# 03_-_DAC8760.net
KiCad netlist of a schematic drawn in Altium Designer
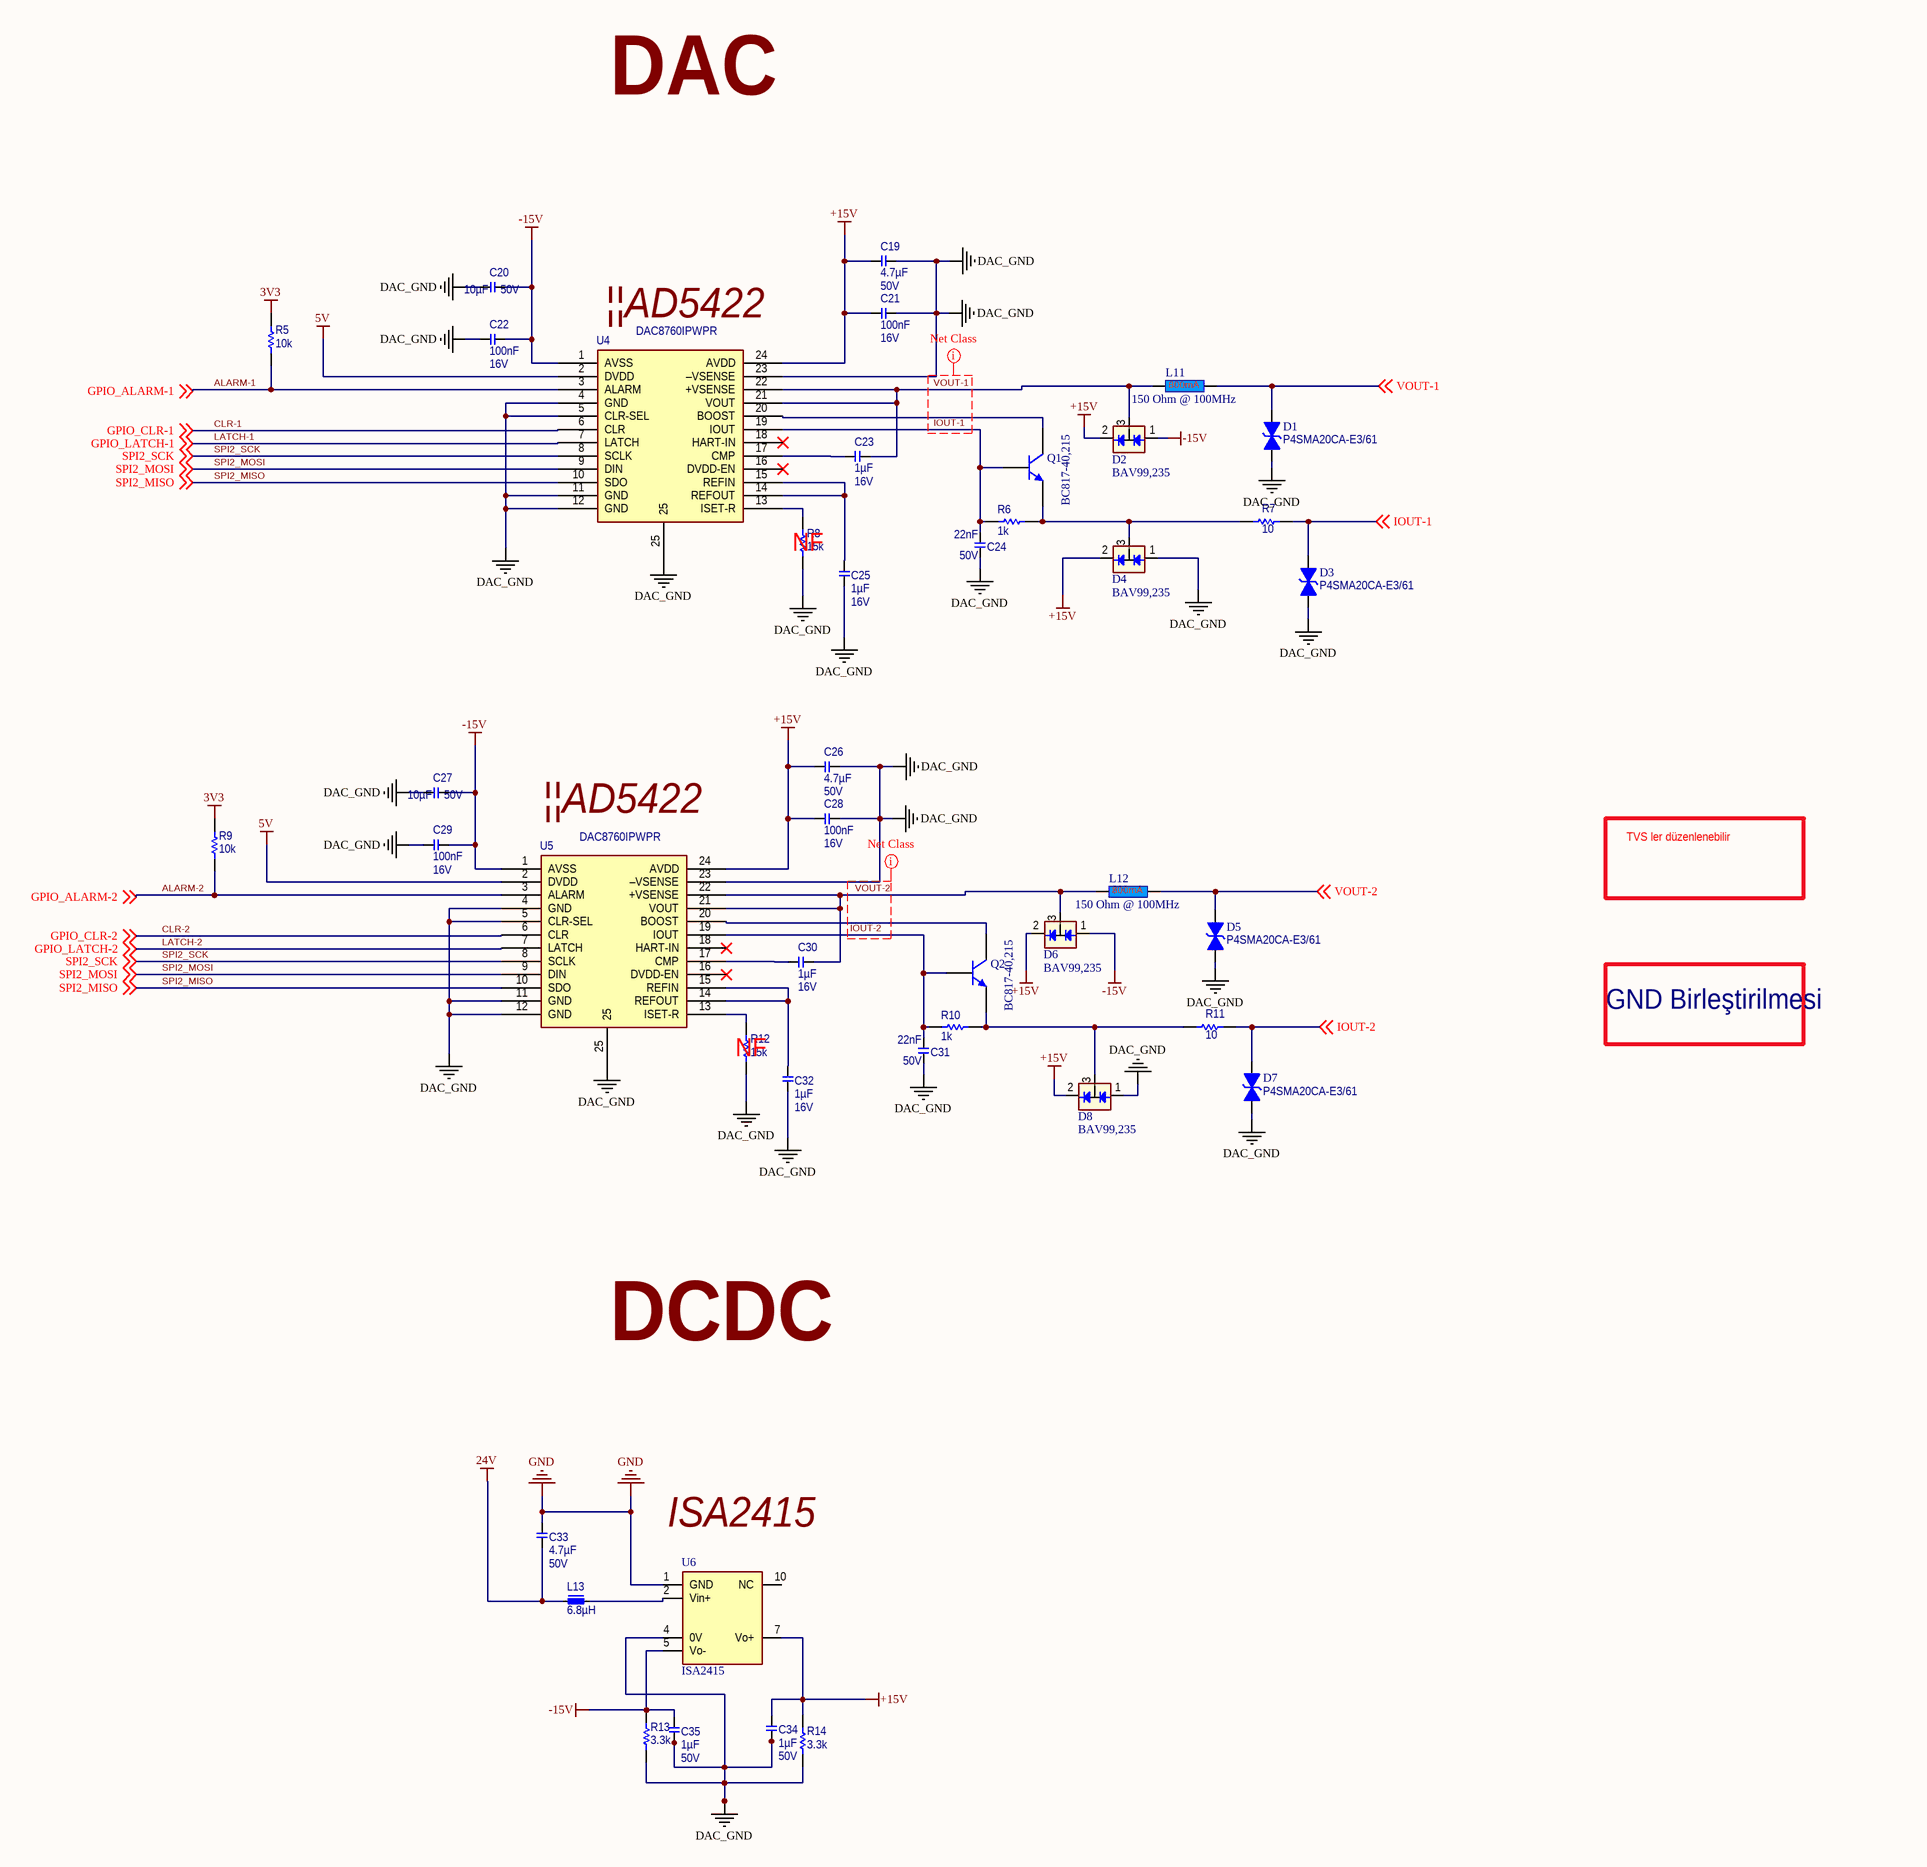
[diagram p0: [03] - DAC8760.SchDoc]

(export (version "E")
  (design (tool "Eeschema 10.0.6"))
  (components
    (comp (ref "C19")
      (value "4.7UF 50V X7R")
      (footprint "C1206")
      (description "CAP CER 4.7UF 50V X7R 1206")
      (fields
        (field (name "MANUFACTURER") "Samsung Electro-Mechanics America, Inc.")
        (field (name "MANUFACTURER PART NUMBER") "CL31B475KBHNNNE")
        (field (name "CAPACITANCE") "4.7µF")
        (field (name "VOLTAGE - RATED") "50V")
      )
      (libsource (lib "CPU_STM_080816") (part "C-4.7UF,50V,1206"))
    )
    (comp (ref "C20")
      (value "10UF 50V X5R")
      (footprint "C0805")
      (description "CAP CER 10UF 50V X7R 1206")
      (fields
        (field (name "MANUFACTURER") "Samsung Electro-Mechanics America, Inc.")
        (field (name "MANUFACTURER PART NUMBER") "CL31B106KBHNNNE")
        (field (name "CAPACITANCE") "10µF")
        (field (name "VOLTAGE - RATED") "50V")
      )
      (libsource (lib "CPU_STM_080816") (part "C-10UF,50V,0805"))
    )
    (comp (ref "C21")
      (value "100nF")
      (footprint "C0805")
      (description "AVX - 0805YA103JAT2A - CAP, MLCC, C0G/NP0, 10NF, 16V, 0805")
      (fields
        (field (name "MANUFACTURER") "AVX")
        (field (name "MANUFACTURER PART NUMBER") "0805YA103JAT2A")
        (field (name "CAPACITANCE") "100nF")
        (field (name "VOLTAGE - RATED") "16V")
      )
      (libsource (lib "CPU_STM_080816") (part "C-100NF,16V,0805"))
    )
    (comp (ref "C22")
      (value "100nF")
      (footprint "C0805")
      (description "AVX - 0805YA103JAT2A - CAP, MLCC, C0G/NP0, 10NF, 16V, 0805")
      (fields
        (field (name "MANUFACTURER") "AVX")
        (field (name "MANUFACTURER PART NUMBER") "0805YA103JAT2A")
        (field (name "CAPACITANCE") "100nF")
        (field (name "VOLTAGE - RATED") "16V")
      )
      (libsource (lib "CPU_STM_080816") (part "C-100NF,16V,0805"))
    )
    (comp (ref "C23")
      (value "1µF")
      (footprint "C0805")
      (description "AVX - 0805YC105KAT2A - CAP, MLCC, X7R, 1UF, 16V, 0805")
      (fields
        (field (name "MANUFACTURER") "AVX Corporation")
        (field (name "MANUFACTURER PART NUMBER") "0805YC105KAT2A")
        (field (name "CAPACITANCE") "1µF")
        (field (name "VOLTAGE - RATED") "16V")
      )
      (libsource (lib "CPU_STM_080816") (part "C-1UF,16V,0805"))
    )
    (comp (ref "C24")
      (value "22NF 50V X7R")
      (footprint "C0805")
      (description "CAP CER 0.022UF 50V X7R 0805")
      (fields
        (field (name "MANUFACTURER") "Kemet")
        (field (name "MANUFACTURER PART NUMBER") "C0805C223K5RACTU")
        (field (name "CAPACITANCE") "22nF")
        (field (name "VOLTAGE - RATED") "50V")
      )
      (libsource (lib "CPU_STM_080816") (part "C-22NF,50V"))
    )
    (comp (ref "C25")
      (value "1µF")
      (footprint "C0805")
      (description "AVX - 0805YC105KAT2A - CAP, MLCC, X7R, 1UF, 16V, 0805")
      (fields
        (field (name "MANUFACTURER") "AVX Corporation")
        (field (name "MANUFACTURER PART NUMBER") "0805YC105KAT2A")
        (field (name "CAPACITANCE") "1µF")
        (field (name "VOLTAGE - RATED") "16V")
      )
      (libsource (lib "CPU_STM_080816") (part "C-1UF,16V,0805"))
    )
    (comp (ref "C26")
      (value "4.7UF 50V X7R")
      (footprint "C1206")
      (description "CAP CER 4.7UF 50V X7R 1206")
      (fields
        (field (name "MANUFACTURER") "Samsung Electro-Mechanics America, Inc.")
        (field (name "MANUFACTURER PART NUMBER") "CL31B475KBHNNNE")
        (field (name "CAPACITANCE") "4.7µF")
        (field (name "VOLTAGE - RATED") "50V")
      )
      (libsource (lib "CPU_STM_080816") (part "C-4.7UF,50V,1206"))
    )
    (comp (ref "C27")
      (value "10UF 50V X5R")
      (footprint "C0805")
      (description "CAP CER 10UF 50V X7R 1206")
      (fields
        (field (name "MANUFACTURER") "Samsung Electro-Mechanics America, Inc.")
        (field (name "MANUFACTURER PART NUMBER") "CL31B106KBHNNNE")
        (field (name "CAPACITANCE") "10µF")
        (field (name "VOLTAGE - RATED") "50V")
      )
      (libsource (lib "CPU_STM_080816") (part "C-10UF,50V,0805"))
    )
    (comp (ref "C28")
      (value "100nF")
      (footprint "C0805")
      (description "AVX - 0805YA103JAT2A - CAP, MLCC, C0G/NP0, 10NF, 16V, 0805")
      (fields
        (field (name "MANUFACTURER") "AVX")
        (field (name "MANUFACTURER PART NUMBER") "0805YA103JAT2A")
        (field (name "CAPACITANCE") "100nF")
        (field (name "VOLTAGE - RATED") "16V")
      )
      (libsource (lib "CPU_STM_080816") (part "C-100NF,16V,0805"))
    )
    (comp (ref "C29")
      (value "100nF")
      (footprint "C0805")
      (description "AVX - 0805YA103JAT2A - CAP, MLCC, C0G/NP0, 10NF, 16V, 0805")
      (fields
        (field (name "MANUFACTURER") "AVX")
        (field (name "MANUFACTURER PART NUMBER") "0805YA103JAT2A")
        (field (name "CAPACITANCE") "100nF")
        (field (name "VOLTAGE - RATED") "16V")
      )
      (libsource (lib "CPU_STM_080816") (part "C-100NF,16V,0805"))
    )
    (comp (ref "C30")
      (value "1µF")
      (footprint "C0805")
      (description "AVX - 0805YC105KAT2A - CAP, MLCC, X7R, 1UF, 16V, 0805")
      (fields
        (field (name "MANUFACTURER") "AVX Corporation")
        (field (name "MANUFACTURER PART NUMBER") "0805YC105KAT2A")
        (field (name "CAPACITANCE") "1µF")
        (field (name "VOLTAGE - RATED") "16V")
      )
      (libsource (lib "CPU_STM_080816") (part "C-1UF,16V,0805"))
    )
    (comp (ref "C31")
      (value "22NF 50V X7R")
      (footprint "C0805")
      (description "CAP CER 0.022UF 50V X7R 0805")
      (fields
        (field (name "MANUFACTURER") "Kemet")
        (field (name "MANUFACTURER PART NUMBER") "C0805C223K5RACTU")
        (field (name "CAPACITANCE") "22nF")
        (field (name "VOLTAGE - RATED") "50V")
      )
      (libsource (lib "CPU_STM_080816") (part "C-22NF,50V"))
    )
    (comp (ref "C32")
      (value "1µF")
      (footprint "C0805")
      (description "AVX - 0805YC105KAT2A - CAP, MLCC, X7R, 1UF, 16V, 0805")
      (fields
        (field (name "MANUFACTURER") "AVX Corporation")
        (field (name "MANUFACTURER PART NUMBER") "0805YC105KAT2A")
        (field (name "CAPACITANCE") "1µF")
        (field (name "VOLTAGE - RATED") "16V")
      )
      (libsource (lib "CPU_STM_080816") (part "C-1UF,16V,0805"))
    )
    (comp (ref "C33")
      (value "4.7UF 50V X7R")
      (footprint "C1206")
      (description "CAP CER 4.7UF 50V X7R 1206")
      (fields
        (field (name "MANUFACTURER") "Samsung Electro-Mechanics America, Inc.")
        (field (name "MANUFACTURER PART NUMBER") "CL31B475KBHNNNE")
        (field (name "CAPACITANCE") "4.7µF")
        (field (name "VOLTAGE - RATED") "50V")
      )
      (libsource (lib "CPU_STM_080816") (part "C-4.7UF,50V,1206"))
    )
    (comp (ref "C34")
      (value "1UF 50V X7R")
      (footprint "C0805")
      (description "CAP CER 1UF 50V X7R 0805")
      (fields
        (field (name "MANUFACTURER") "Samsung Electro-Mechanics America, Inc.")
        (field (name "MANUFACTURER PART NUMBER") "CL21B105KBFNNNE")
        (field (name "CAPACITANCE") "1µF")
        (field (name "VOLTAGE - RATED") "50V")
      )
      (libsource (lib "CPU_STM_080816") (part "C-1UF,50V"))
    )
    (comp (ref "C35")
      (value "1UF 50V X7R")
      (footprint "C0805")
      (description "CAP CER 1UF 50V X7R 0805")
      (fields
        (field (name "MANUFACTURER") "Samsung Electro-Mechanics America, Inc.")
        (field (name "MANUFACTURER PART NUMBER") "CL21B105KBFNNNE")
        (field (name "CAPACITANCE") "1µF")
        (field (name "VOLTAGE - RATED") "50V")
      )
      (libsource (lib "CPU_STM_080816") (part "C-1UF,50V"))
    )
    (comp (ref "D1")
      (value "TVS DIODE 15VWM 24.4VC SMC")
      (footprint "DO-214Ac")
      (description "TVS DIODE 17.1VWM 27.7VC SMA")
      (fields
        (field (name "MANUFACTURER") "Vishay Semiconductor Diodes Division")
        (field (name "MANUFACTURER PART NUMBER") "P4SMA20CA-E3/61")
      )
      (libsource (lib "CPU_STM_080816") (part "D-P4SMA20CA TVS DIODE"))
    )
    (comp (ref "D2")
      (value "BAV99")
      (footprint "SOT23-3 - Number")
      (description "DIODE ARRAY GP 100V 215MA SOT23")
      (fields
        (field (name "MANUFACTURER") "NXP Semiconductors")
        (field (name "MANUFACTURER PART NUMBER") "BAV99,235")
      )
      (libsource (lib "CPU_STM_080816") (part "D-BAV99,235"))
    )
    (comp (ref "D3")
      (value "TVS DIODE 15VWM 24.4VC SMC")
      (footprint "DO-214Ac")
      (description "TVS DIODE 17.1VWM 27.7VC SMA")
      (fields
        (field (name "MANUFACTURER") "Vishay Semiconductor Diodes Division")
        (field (name "MANUFACTURER PART NUMBER") "P4SMA20CA-E3/61")
      )
      (libsource (lib "CPU_STM_080816") (part "D-P4SMA20CA TVS DIODE"))
    )
    (comp (ref "D4")
      (value "BAV99")
      (footprint "SOT23-3 - Number")
      (description "DIODE ARRAY GP 100V 215MA SOT23")
      (fields
        (field (name "MANUFACTURER") "NXP Semiconductors")
        (field (name "MANUFACTURER PART NUMBER") "BAV99,235")
      )
      (libsource (lib "CPU_STM_080816") (part "D-BAV99,235"))
    )
    (comp (ref "D5")
      (value "TVS DIODE 15VWM 24.4VC SMC")
      (footprint "DO-214Ac")
      (description "TVS DIODE 17.1VWM 27.7VC SMA")
      (fields
        (field (name "MANUFACTURER") "Vishay Semiconductor Diodes Division")
        (field (name "MANUFACTURER PART NUMBER") "P4SMA20CA-E3/61")
      )
      (libsource (lib "CPU_STM_080816") (part "D-P4SMA20CA TVS DIODE"))
    )
    (comp (ref "D6")
      (value "BAV99")
      (footprint "SOT23-3 - Number")
      (description "DIODE ARRAY GP 100V 215MA SOT23")
      (fields
        (field (name "MANUFACTURER") "NXP Semiconductors")
        (field (name "MANUFACTURER PART NUMBER") "BAV99,235")
      )
      (libsource (lib "CPU_STM_080816") (part "D-BAV99,235"))
    )
    (comp (ref "D7")
      (value "TVS DIODE 15VWM 24.4VC SMC")
      (footprint "DO-214Ac")
      (description "TVS DIODE 17.1VWM 27.7VC SMA")
      (fields
        (field (name "MANUFACTURER") "Vishay Semiconductor Diodes Division")
        (field (name "MANUFACTURER PART NUMBER") "P4SMA20CA-E3/61")
      )
      (libsource (lib "CPU_STM_080816") (part "D-P4SMA20CA TVS DIODE"))
    )
    (comp (ref "D8")
      (value "BAV99")
      (footprint "SOT23-3 - Number")
      (description "DIODE ARRAY GP 100V 215MA SOT23")
      (fields
        (field (name "MANUFACTURER") "NXP Semiconductors")
        (field (name "MANUFACTURER PART NUMBER") "BAV99,235")
      )
      (libsource (lib "CPU_STM_080816") (part "D-BAV99,235"))
    )
    (comp (ref "L11")
      (value "150 Ohm @ 100MHz")
      (footprint "0805")
      (description "FERRITE 800MA 150 OHM 0805 SMD")
      (fields
        (field (name "MANUFACTURER") "Laird-Signal Integrity Products")
        (field (name "MANUFACTURER PART NUMBER") "LI0805H151R-10")
        (field (name "IMPEDANCE @ FREQUENCY") "150 Ohm @ 100MHz")
      )
      (libsource (lib "CPU_STM_080816") (part "L-150OHM,800MA"))
    )
    (comp (ref "L12")
      (value "150 Ohm @ 100MHz")
      (footprint "0805")
      (description "FERRITE 800MA 150 OHM 0805 SMD")
      (fields
        (field (name "MANUFACTURER") "Laird-Signal Integrity Products")
        (field (name "MANUFACTURER PART NUMBER") "LI0805H151R-10")
        (field (name "IMPEDANCE @ FREQUENCY") "150 Ohm @ 100MHz")
      )
      (libsource (lib "CPU_STM_080816") (part "L-150OHM,800MA"))
    )
    (comp (ref "L13")
      (value "6.8UH 550MA")
      (footprint "0805")
      (description "FIXED IND 6.8UH 550MA 250 MOHM")
      (fields
        (field (name "MANUFACTURER") "TDK Corporation")
        (field (name "MANUFACTURER PART NUMBER") "MLZ2012N6R8LT000")
        (field (name "INDUCTANCE") "6.8µH")
      )
      (libsource (lib "CPU_STM_080816") (part "L-6.8UH,550mA,0805"))
    )
    (comp (ref "Q1")
      (value "BC817-40,215")
      (footprint "SO-G3/Y1")
      (description "TRANS NPN 45V 0.5A SOT23")
      (fields
        (field (name "MANUFACTURER") "NXP Semiconductors")
        (field (name "MANUFACTURER PART NUMBER") "BC817-40,215")
      )
      (libsource (lib "CPU_STM_080816") (part "T-BC817-40 NPN"))
    )
    (comp (ref "Q2")
      (value "BC817-40,215")
      (footprint "SO-G3/Y1")
      (description "TRANS NPN 45V 0.5A SOT23")
      (fields
        (field (name "MANUFACTURER") "NXP Semiconductors")
        (field (name "MANUFACTURER PART NUMBER") "BC817-40,215")
      )
      (libsource (lib "CPU_STM_080816") (part "T-BC817-40 NPN"))
    )
    (comp (ref "R5")
      (value "R-10K,%1,0805")
      (footprint "R0805")
      (description "RES SMD 10K OHM 1% 1/8W 0805")
      (fields
        (field (name "MANUFACTURER") "Yageo")
        (field (name "MANUFACTURER PART NUMBER") "RC0805FR-0710KL")
        (field (name "RESISTANCE (OHMS)") "10k")
      )
      (libsource (lib "CPU_STM_080816") (part "R-10K,%1,0805"))
    )
    (comp (ref "R6")
      (value "R-1K,0805")
      (footprint "R0805")
      (description "BOURNS - CR0805-FX-1001ELF - RESISTOR, 1K, 0.125W, 1%")
      (fields
        (field (name "MANUFACTURER") "Bourns Inc.")
        (field (name "MANUFACTURER PART NUMBER") "CR0805-FX-1001ELF")
        (field (name "RESISTANCE (OHMS)") "1k")
      )
      (libsource (lib "CPU_STM_080816") (part "R-1K,0805"))
    )
    (comp (ref "R7")
      (value "10 OHM")
      (footprint "R0805")
      (description "RES SMD 10 OHM 1% 1/8W 0805")
      (fields
        (field (name "MANUFACTURER") "Yageo")
        (field (name "MANUFACTURER PART NUMBER") "RC0805FR-0710RL")
        (field (name "RESISTANCE (OHMS)") "10")
      )
      (libsource (lib "CPU_STM_080816") (part "R-10R,0805"))
    )
    (comp (ref "R8")
      (value "15K OHM")
      (footprint "R0805")
      (description "RES SMD 15K OHM 5% 1/8W 0805")
      (fields
        (field (name "MANUFACTURER") "Yageo")
        (field (name "MANUFACTURER PART NUMBER") "RC0805JR-0715KL")
        (field (name "RESISTANCE (OHMS)") "15k")
      )
      (libsource (lib "CPU_STM_080816") (part "R-15k,0805"))
    )
    (comp (ref "R9")
      (value "R-10K,%1,0805")
      (footprint "R0805")
      (description "RES SMD 10K OHM 1% 1/8W 0805")
      (fields
        (field (name "MANUFACTURER") "Yageo")
        (field (name "MANUFACTURER PART NUMBER") "RC0805FR-0710KL")
        (field (name "RESISTANCE (OHMS)") "10k")
      )
      (libsource (lib "CPU_STM_080816") (part "R-10K,%1,0805"))
    )
    (comp (ref "R10")
      (value "R-1K,0805")
      (footprint "R0805")
      (description "BOURNS - CR0805-FX-1001ELF - RESISTOR, 1K, 0.125W, 1%")
      (fields
        (field (name "MANUFACTURER") "Bourns Inc.")
        (field (name "MANUFACTURER PART NUMBER") "CR0805-FX-1001ELF")
        (field (name "RESISTANCE (OHMS)") "1k")
      )
      (libsource (lib "CPU_STM_080816") (part "R-1K,0805"))
    )
    (comp (ref "R11")
      (value "10 OHM")
      (footprint "R0805")
      (description "RES SMD 10 OHM 1% 1/8W 0805")
      (fields
        (field (name "MANUFACTURER") "Yageo")
        (field (name "MANUFACTURER PART NUMBER") "RC0805FR-0710RL")
        (field (name "RESISTANCE (OHMS)") "10")
      )
      (libsource (lib "CPU_STM_080816") (part "R-10R,0805"))
    )
    (comp (ref "R12")
      (value "15K OHM")
      (footprint "R0805")
      (description "RES SMD 15K OHM 5% 1/8W 0805")
      (fields
        (field (name "MANUFACTURER") "Yageo")
        (field (name "MANUFACTURER PART NUMBER") "RC0805JR-0715KL")
        (field (name "RESISTANCE (OHMS)") "15k")
      )
      (libsource (lib "CPU_STM_080816") (part "R-15k,0805"))
    )
    (comp (ref "R13")
      (value "3.3K OHM 0805")
      (footprint "R0805")
      (description "RES SMD 3.3K OHM 5% 1/8W 0805")
      (fields
        (field (name "MANUFACTURER") "Yageo")
        (field (name "MANUFACTURER PART NUMBER") "RC0805JR-073K3L")
        (field (name "RESISTANCE (OHMS)") "3.3k")
      )
      (libsource (lib "CPU_STM_080816") (part "R-3.3K,0805"))
    )
    (comp (ref "R14")
      (value "3.3K OHM 0805")
      (footprint "R0805")
      (description "RES SMD 3.3K OHM 5% 1/8W 0805")
      (fields
        (field (name "MANUFACTURER") "Yageo")
        (field (name "MANUFACTURER PART NUMBER") "RC0805JR-073K3L")
        (field (name "RESISTANCE (OHMS)") "3.3k")
      )
      (libsource (lib "CPU_STM_080816") (part "R-3.3K,0805"))
    )
    (comp (ref "U4")
      (value "IC-DAC8760IPWPR")
      (footprint "TSSOP-24")
      (description "IC DAC 1CH 16BIT PROGR 24HTSSOP")
      (fields
        (field (name "MANUFACTURER") "Texas Instruments")
        (field (name "MANUFACTURER PART NUMBER") "DAC8760IPWPR")
      )
      (libsource (lib "CPU_STM_080816") (part "IC-DAC8760IPWPR"))
    )
    (comp (ref "U5")
      (value "IC-DAC8760IPWPR")
      (footprint "TSSOP-24")
      (description "IC DAC 1CH 16BIT PROGR 24HTSSOP")
      (fields
        (field (name "MANUFACTURER") "Texas Instruments")
        (field (name "MANUFACTURER PART NUMBER") "DAC8760IPWPR")
      )
      (libsource (lib "CPU_STM_080816") (part "IC-DAC8760IPWPR"))
    )
    (comp (ref "U6")
      (value "DC/DC CONV")
      (footprint "ISA2415")
      (description "DC/DC CONV 1W SMD DUAL OUT")
      (fields (field (name "MANUFACTURER") "XP Power") (field (name "MANUFACTURER PART NUMBER") "ISA2415"))
      (libsource (lib "CPU_STM_080816") (part "IC-ISA2415"))
    )
  )
  (nets
    (net (code "1") (name "+15V") (class "Default")
      (node (ref "C19") (pin "1") (pinfunction "1_1") (pintype "passive"))
      (node (ref "C21") (pin "1") (pinfunction "1_1") (pintype "passive"))
      (node (ref "C26") (pin "1") (pinfunction "1_1") (pintype "passive"))
      (node (ref "C28") (pin "1") (pinfunction "1_1") (pintype "passive"))
      (node (ref "C34") (pin "2") (pinfunction "2_2") (pintype "passive"))
      (node (ref "D2") (pin "2") (pinfunction "D-_2") (pintype "power_in"))
      (node (ref "D4") (pin "2") (pinfunction "D-_2") (pintype "power_in"))
      (node (ref "D6") (pin "2") (pinfunction "D-_2") (pintype "power_in"))
      (node (ref "D8") (pin "2") (pinfunction "D-_2") (pintype "power_in"))
      (node (ref "R14") (pin "2") (pinfunction "2_2") (pintype "passive"))
      (node (ref "U4") (pin "24") (pinfunction "AVDD_24") (pintype "passive"))
      (node (ref "U5") (pin "24") (pinfunction "AVDD_24") (pintype "passive"))
      (node (ref "U6") (pin "7") (pinfunction "Vo+_7") (pintype "passive"))
    )
    (net (code "2") (name "-15V") (class "Default")
      (node (ref "C20") (pin "2") (pinfunction "2_2") (pintype "passive"))
      (node (ref "C22") (pin "2") (pinfunction "2_2") (pintype "passive"))
      (node (ref "C27") (pin "2") (pinfunction "2_2") (pintype "passive"))
      (node (ref "C29") (pin "2") (pinfunction "2_2") (pintype "passive"))
      (node (ref "C35") (pin "2") (pinfunction "2_2") (pintype "passive"))
      (node (ref "D2") (pin "1") (pinfunction "D+_1") (pintype "power_in"))
      (node (ref "D6") (pin "1") (pinfunction "D+_1") (pintype "power_in"))
      (node (ref "R13") (pin "2") (pinfunction "2_2") (pintype "passive"))
      (node (ref "U4") (pin "1") (pinfunction "AVSS_1") (pintype "passive"))
      (node (ref "U5") (pin "1") (pinfunction "AVSS_1") (pintype "passive"))
      (node (ref "U6") (pin "5") (pinfunction "Vo-_5") (pintype "passive"))
    )
    (net (code "3") (name "3V3") (class "Default")
      (node (ref "R5") (pin "2") (pinfunction "2_2") (pintype "passive"))
      (node (ref "R9") (pin "2") (pinfunction "2_2") (pintype "passive"))
    )
    (net (code "4") (name "5V") (class "Default")
      (node (ref "U4") (pin "2") (pinfunction "DVDD_2") (pintype "passive"))
      (node (ref "U5") (pin "2") (pinfunction "DVDD_2") (pintype "passive"))
    )
    (net (code "5") (name "24V") (class "Default")
      (node (ref "C33") (pin "1") (pinfunction "1_1") (pintype "passive"))
      (node (ref "L13") (pin "1") (pinfunction "1_1") (pintype "passive"))
    )
    (net (code "6") (name "DAC_GND") (class "Default")
      (node (ref "C19") (pin "2") (pinfunction "2_2") (pintype "passive"))
      (node (ref "C20") (pin "1") (pinfunction "1_1") (pintype "passive"))
      (node (ref "C21") (pin "2") (pinfunction "2_2") (pintype "passive"))
      (node (ref "C22") (pin "1") (pinfunction "1_1") (pintype "passive"))
      (node (ref "C24") (pin "1") (pinfunction "1_1") (pintype "passive"))
      (node (ref "C25") (pin "1") (pinfunction "1_1") (pintype "passive"))
      (node (ref "C26") (pin "2") (pinfunction "2_2") (pintype "passive"))
      (node (ref "C27") (pin "1") (pinfunction "1_1") (pintype "passive"))
      (node (ref "C28") (pin "2") (pinfunction "2_2") (pintype "passive"))
      (node (ref "C29") (pin "1") (pinfunction "1_1") (pintype "passive"))
      (node (ref "C31") (pin "1") (pinfunction "1_1") (pintype "passive"))
      (node (ref "C32") (pin "1") (pinfunction "1_1") (pintype "passive"))
      (node (ref "C34") (pin "1") (pinfunction "1_1") (pintype "passive"))
      (node (ref "C35") (pin "1") (pinfunction "1_1") (pintype "passive"))
      (node (ref "D1") (pin "2") (pinfunction "ANODE_2") (pintype "passive"))
      (node (ref "D3") (pin "2") (pinfunction "ANODE_2") (pintype "passive"))
      (node (ref "D4") (pin "1") (pinfunction "D+_1") (pintype "power_in"))
      (node (ref "D5") (pin "2") (pinfunction "ANODE_2") (pintype "passive"))
      (node (ref "D7") (pin "2") (pinfunction "ANODE_2") (pintype "passive"))
      (node (ref "D8") (pin "1") (pinfunction "D+_1") (pintype "power_in"))
      (node (ref "R12") (pin "1") (pinfunction "1_1") (pintype "passive"))
      (node (ref "R13") (pin "1") (pinfunction "1_1") (pintype "passive"))
      (node (ref "R14") (pin "1") (pinfunction "1_1") (pintype "passive"))
      (node (ref "R8") (pin "1") (pinfunction "1_1") (pintype "passive"))
      (node (ref "U4") (pin "11") (pinfunction "GND_11") (pintype "passive"))
      (node (ref "U4") (pin "12") (pinfunction "GND_12") (pintype "passive"))
      (node (ref "U4") (pin "23") (pinfunction "–VSENSE_23") (pintype "passive"))
      (node (ref "U4") (pin "25") (pinfunction "25_25") (pintype "passive"))
      (node (ref "U4") (pin "4") (pinfunction "GND_4") (pintype "passive"))
      (node (ref "U4") (pin "5") (pinfunction "CLR-SEL_5") (pintype "passive"))
      (node (ref "U5") (pin "11") (pinfunction "GND_11") (pintype "passive"))
      (node (ref "U5") (pin "12") (pinfunction "GND_12") (pintype "passive"))
      (node (ref "U5") (pin "23") (pinfunction "–VSENSE_23") (pintype "passive"))
      (node (ref "U5") (pin "25") (pinfunction "25_25") (pintype "passive"))
      (node (ref "U5") (pin "4") (pinfunction "GND_4") (pintype "passive"))
      (node (ref "U5") (pin "5") (pinfunction "CLR-SEL_5") (pintype "passive"))
      (node (ref "U6") (pin "4") (pinfunction "0V_4") (pintype "passive"))
    )
    (net (code "7") (name "GND") (class "Default")
      (node (ref "C33") (pin "2") (pinfunction "2_2") (pintype "passive"))
      (node (ref "U6") (pin "1") (pinfunction "GND_1") (pintype "passive"))
    )
    (net (code "8") (name "GPIO_ALARM-1") (class "Default")
      (node (ref "R5") (pin "1") (pinfunction "1_1") (pintype "passive"))
      (node (ref "U4") (pin "3") (pinfunction "ALARM_3") (pintype "passive"))
    )
    (net (code "9") (name "GPIO_ALARM-2") (class "Default")
      (node (ref "R9") (pin "1") (pinfunction "1_1") (pintype "passive"))
      (node (ref "U5") (pin "3") (pinfunction "ALARM_3") (pintype "passive"))
    )
    (net (code "10") (name "GPIO_CLR-1") (class "Default")
      (node (ref "U4") (pin "6") (pinfunction "CLR_6") (pintype "passive"))
    )
    (net (code "11") (name "GPIO_CLR-2") (class "Default")
      (node (ref "U5") (pin "6") (pinfunction "CLR_6") (pintype "passive"))
    )
    (net (code "12") (name "GPIO_LATCH-1") (class "Default")
      (node (ref "U4") (pin "7") (pinfunction "LATCH_7") (pintype "passive"))
    )
    (net (code "13") (name "GPIO_LATCH-2") (class "Default")
      (node (ref "U5") (pin "7") (pinfunction "LATCH_7") (pintype "passive"))
    )
    (net (code "14") (name "IOUT-1") (class "Default")
      (node (ref "C24") (pin "2") (pinfunction "2_2") (pintype "passive"))
      (node (ref "D3") (pin "1") (pinfunction "CATHODE_1") (pintype "passive"))
      (node (ref "Q1") (pin "1") (pinfunction "B_1") (pintype "passive"))
      (node (ref "R6") (pin "1") (pinfunction "1_1") (pintype "passive"))
      (node (ref "R7") (pin "2") (pinfunction "2_2") (pintype "passive"))
      (node (ref "U4") (pin "19") (pinfunction "IOUT_19") (pintype "passive"))
    )
    (net (code "15") (name "IOUT-2") (class "Default")
      (node (ref "C31") (pin "2") (pinfunction "2_2") (pintype "passive"))
      (node (ref "D7") (pin "1") (pinfunction "CATHODE_1") (pintype "passive"))
      (node (ref "Q2") (pin "1") (pinfunction "B_1") (pintype "passive"))
      (node (ref "R10") (pin "1") (pinfunction "1_1") (pintype "passive"))
      (node (ref "R11") (pin "2") (pinfunction "2_2") (pintype "passive"))
      (node (ref "U5") (pin "19") (pinfunction "IOUT_19") (pintype "passive"))
    )
    (net (code "16") (name "Net-(Q1-C)") (class "Default")
      (node (ref "Q1") (pin "3") (pinfunction "C_3") (pintype "passive"))
      (node (ref "U4") (pin "20") (pinfunction "BOOST_20") (pintype "passive"))
    )
    (net (code "17") (name "Net-(Q1-E)") (class "Default")
      (node (ref "D4") (pin "3") (pinfunction "3_3") (pintype "power_in"))
      (node (ref "Q1") (pin "2") (pinfunction "E_2") (pintype "passive"))
      (node (ref "R6") (pin "2") (pinfunction "2_2") (pintype "passive"))
      (node (ref "R7") (pin "1") (pinfunction "1_1") (pintype "passive"))
    )
    (net (code "18") (name "Net-(Q2-C)") (class "Default")
      (node (ref "Q2") (pin "3") (pinfunction "C_3") (pintype "passive"))
      (node (ref "U5") (pin "20") (pinfunction "BOOST_20") (pintype "passive"))
    )
    (net (code "19") (name "Net-(Q2-E)") (class "Default")
      (node (ref "D8") (pin "3") (pinfunction "3_3") (pintype "power_in"))
      (node (ref "Q2") (pin "2") (pinfunction "E_2") (pintype "passive"))
      (node (ref "R10") (pin "2") (pinfunction "2_2") (pintype "passive"))
      (node (ref "R11") (pin "1") (pinfunction "1_1") (pintype "passive"))
    )
    (net (code "20") (name "Net-(U4-CMP)") (class "Default")
      (node (ref "C23") (pin "1") (pinfunction "1_1") (pintype "passive"))
      (node (ref "U4") (pin "17") (pinfunction "CMP_17") (pintype "passive"))
    )
    (net (code "21") (name "Net-(U4-ISET-R)") (class "Default")
      (node (ref "R8") (pin "2") (pinfunction "2_2") (pintype "passive"))
      (node (ref "U4") (pin "13") (pinfunction "ISET-R_13") (pintype "passive"))
    )
    (net (code "22") (name "Net-(U4-REFIN)") (class "Default")
      (node (ref "C25") (pin "2") (pinfunction "2_2") (pintype "passive"))
      (node (ref "U4") (pin "14") (pinfunction "REFOUT_14") (pintype "passive"))
      (node (ref "U4") (pin "15") (pinfunction "REFIN_15") (pintype "passive"))
    )
    (net (code "23") (name "Net-(U5-CMP)") (class "Default")
      (node (ref "C30") (pin "1") (pinfunction "1_1") (pintype "passive"))
      (node (ref "U5") (pin "17") (pinfunction "CMP_17") (pintype "passive"))
    )
    (net (code "24") (name "Net-(U5-ISET-R)") (class "Default")
      (node (ref "R12") (pin "2") (pinfunction "2_2") (pintype "passive"))
      (node (ref "U5") (pin "13") (pinfunction "ISET-R_13") (pintype "passive"))
    )
    (net (code "25") (name "Net-(U5-REFIN)") (class "Default")
      (node (ref "C32") (pin "2") (pinfunction "2_2") (pintype "passive"))
      (node (ref "U5") (pin "14") (pinfunction "REFOUT_14") (pintype "passive"))
      (node (ref "U5") (pin "15") (pinfunction "REFIN_15") (pintype "passive"))
    )
    (net (code "26") (name "Net-(U6-Vin+)") (class "Default")
      (node (ref "L13") (pin "2") (pinfunction "2_2") (pintype "passive"))
      (node (ref "U6") (pin "2") (pinfunction "Vin+_2") (pintype "passive"))
    )
    (net (code "27") (name "SPI2_MISO") (class "Default")
      (node (ref "U4") (pin "10") (pinfunction "SDO_10") (pintype "passive"))
      (node (ref "U5") (pin "10") (pinfunction "SDO_10") (pintype "passive"))
    )
    (net (code "28") (name "SPI2_MOSI") (class "Default")
      (node (ref "U4") (pin "9") (pinfunction "DIN_9") (pintype "passive"))
      (node (ref "U5") (pin "9") (pinfunction "DIN_9") (pintype "passive"))
    )
    (net (code "29") (name "SPI2_SCK") (class "Default")
      (node (ref "U4") (pin "8") (pinfunction "SCLK_8") (pintype "passive"))
      (node (ref "U5") (pin "8") (pinfunction "SCLK_8") (pintype "passive"))
    )
    (net (code "30") (name "VOUT-1") (class "Default")
      (node (ref "C23") (pin "2") (pinfunction "2_2") (pintype "passive"))
      (node (ref "D1") (pin "1") (pinfunction "CATHODE_1") (pintype "passive"))
      (node (ref "D2") (pin "3") (pinfunction "3_3") (pintype "power_in"))
      (node (ref "L11") (pin "1") (pinfunction "1_1") (pintype "passive"))
      (node (ref "L11") (pin "2") (pinfunction "2_2") (pintype "passive"))
      (node (ref "U4") (pin "21") (pinfunction "VOUT_21") (pintype "passive"))
      (node (ref "U4") (pin "22") (pinfunction "+VSENSE_22") (pintype "passive"))
    )
    (net (code "31") (name "VOUT-2") (class "Default")
      (node (ref "C30") (pin "2") (pinfunction "2_2") (pintype "passive"))
      (node (ref "D5") (pin "1") (pinfunction "CATHODE_1") (pintype "passive"))
      (node (ref "D6") (pin "3") (pinfunction "3_3") (pintype "power_in"))
      (node (ref "L12") (pin "1") (pinfunction "1_1") (pintype "passive"))
      (node (ref "L12") (pin "2") (pinfunction "2_2") (pintype "passive"))
      (node (ref "U5") (pin "21") (pinfunction "VOUT_21") (pintype "passive"))
      (node (ref "U5") (pin "22") (pinfunction "+VSENSE_22") (pintype "passive"))
    )
    (net (code "32") (name "unconnected-(U4-DVDD-EN-Pad16)") (class "Default")
      (node (ref "U4") (pin "16") (pinfunction "DVDD-EN_16") (pintype "passive+no_connect"))
    )
    (net (code "33") (name "unconnected-(U4-HART-IN-Pad18)") (class "Default")
      (node (ref "U4") (pin "18") (pinfunction "HART-IN_18") (pintype "passive+no_connect"))
    )
    (net (code "34") (name "unconnected-(U5-DVDD-EN-Pad16)") (class "Default")
      (node (ref "U5") (pin "16") (pinfunction "DVDD-EN_16") (pintype "passive+no_connect"))
    )
    (net (code "35") (name "unconnected-(U5-HART-IN-Pad18)") (class "Default")
      (node (ref "U5") (pin "18") (pinfunction "HART-IN_18") (pintype "passive+no_connect"))
    )
    (net (code "36") (name "unconnected-(U6-NC-Pad10)") (class "Default")
      (node (ref "U6") (pin "10") (pinfunction "NC_10") (pintype "passive"))
    )
  )
)
